# Shutdown_2019_v1_1_1.net
KiCad netlist of a schematic drawn in Altium Designer
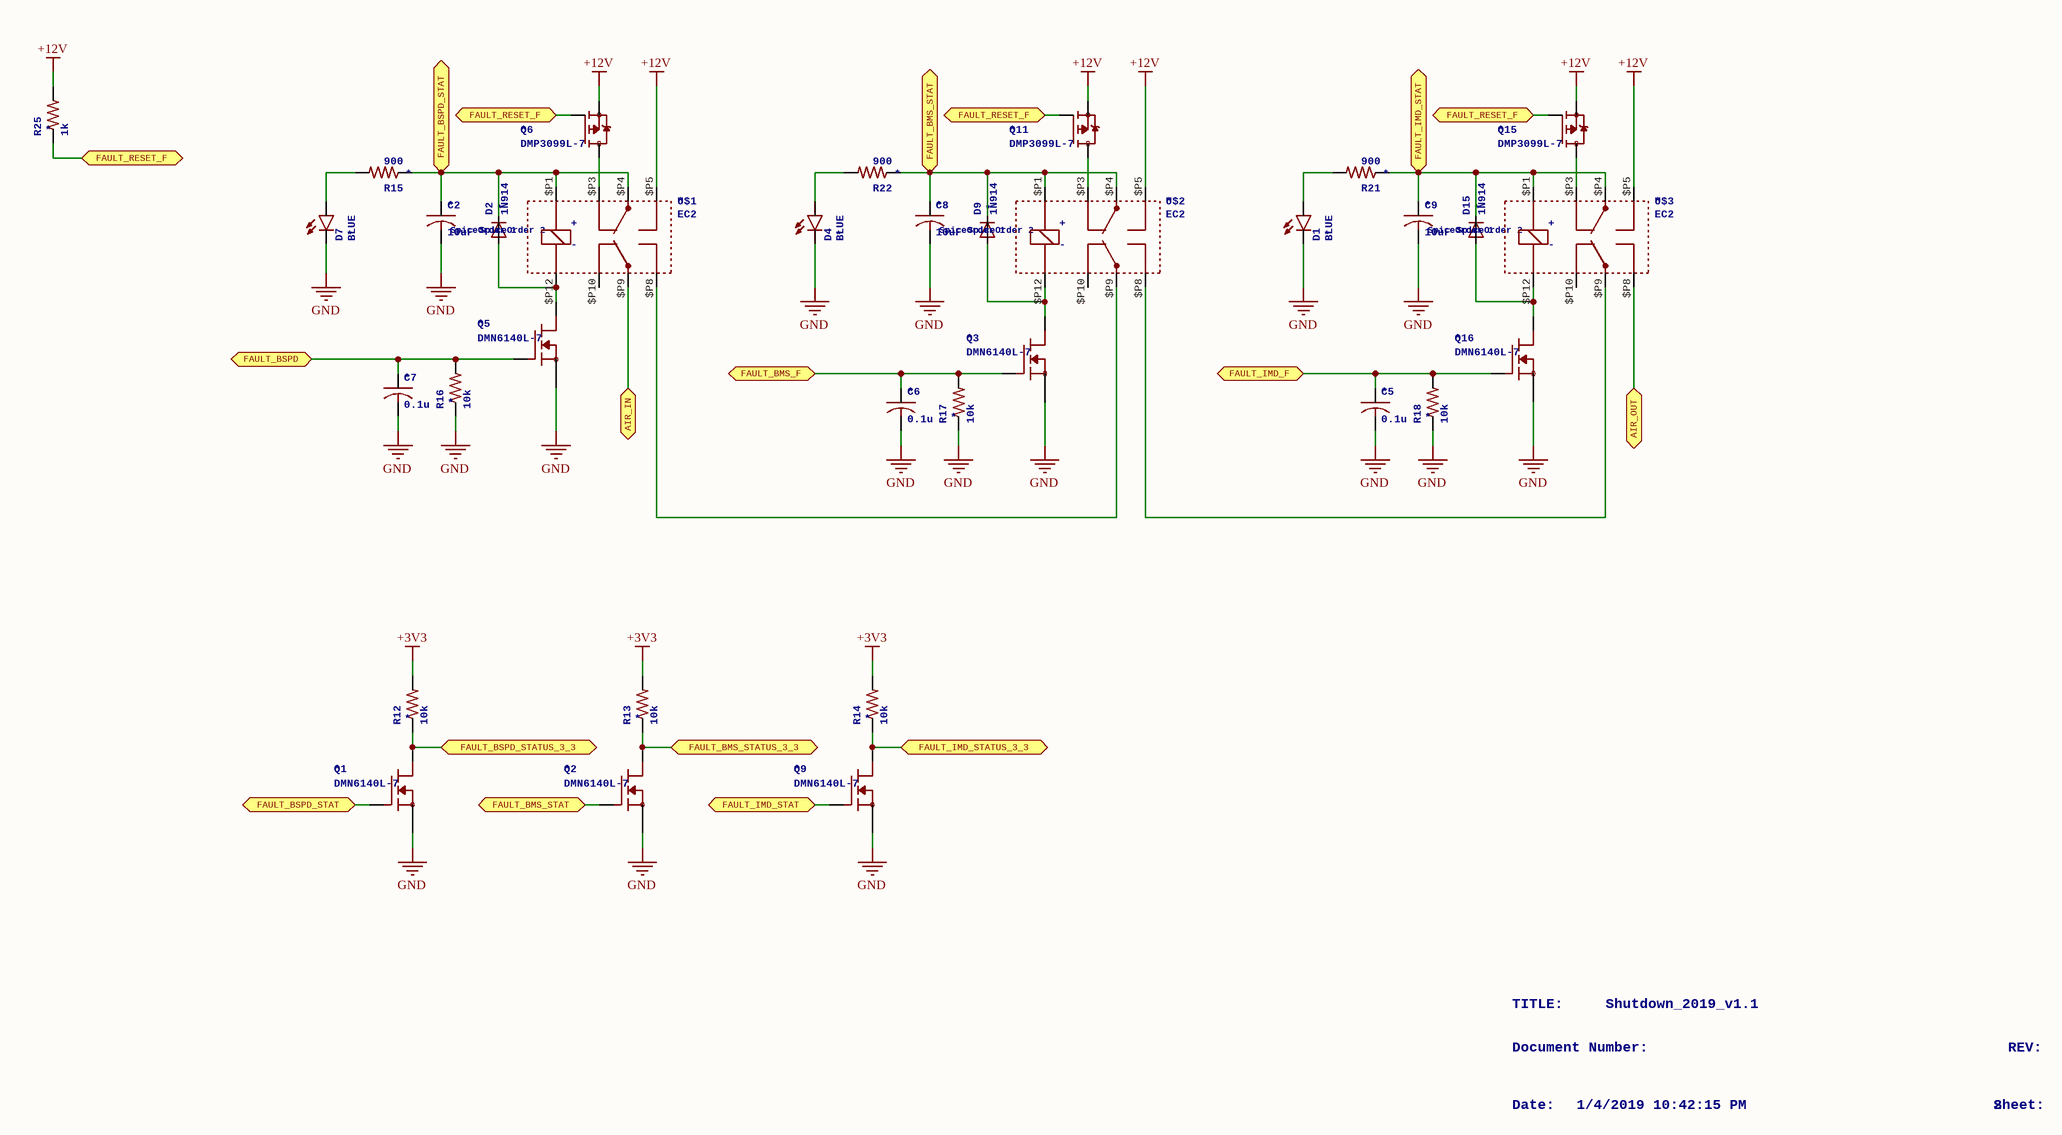
[diagram p0: Shutdown_2019_v1.1_1.SchDoc]

(export (version "E")
  (design (tool "Eeschema 10.0.6"))
  (components
    (comp (ref "C2")
      (value "10uF")
      (footprint "C0805")
      (description "CAPACITOR, American symbol")
      (fields (field (name "NAME") "*"))
      (libsource (lib "rcl") (part "C-USC0805"))
    )
    (comp (ref "C5")
      (value "0.1u")
      (footprint "C0603")
      (description "CAPACITOR, American symbol")
      (fields (field (name "NAME") "*"))
      (libsource (lib "resistor") (part "C-USC0603"))
    )
    (comp (ref "C6")
      (value "0.1u")
      (footprint "C0603")
      (description "CAPACITOR, American symbol")
      (fields (field (name "NAME") "*"))
      (libsource (lib "resistor") (part "C-USC0603"))
    )
    (comp (ref "C7")
      (value "0.1u")
      (footprint "C0603")
      (description "CAPACITOR, American symbol")
      (fields (field (name "NAME") "*"))
      (libsource (lib "resistor") (part "C-USC0603"))
    )
    (comp (ref "C8")
      (value "10uF")
      (footprint "C0805")
      (description "CAPACITOR, American symbol")
      (fields (field (name "NAME") "*"))
      (libsource (lib "rcl") (part "C-USC0805"))
    )
    (comp (ref "C9")
      (value "10uF")
      (footprint "C0805")
      (description "CAPACITOR, American symbol")
      (fields (field (name "NAME") "*"))
      (libsource (lib "rcl") (part "C-USC0805"))
    )
    (comp (ref "D1")
      (value "BLUE")
      (footprint "LED-0603")
      (fields (field (name "NAME") "*"))
      (libsource (lib "SparkFun-LED") (part "LED-BLUE0603"))
    )
    (comp (ref "D2")
      (value "1N914")
      (footprint "SOD323-F")
      (fields
        (field (name "NAME") "*")
        (field (name "SPICEORDER1") "SpiceOrder 1")
        (field (name "SPICEORDER2") "SpiceOrder 2")
      )
      (libsource (lib "Diodes") (part "1N914"))
    )
    (comp (ref "D4")
      (value "BLUE")
      (footprint "LED-0603")
      (fields (field (name "NAME") "*"))
      (libsource (lib "SparkFun-LED") (part "LED-BLUE0603"))
    )
    (comp (ref "D7")
      (value "BLUE")
      (footprint "LED-0603")
      (fields (field (name "NAME") "*"))
      (libsource (lib "SparkFun-LED") (part "LED-BLUE0603"))
    )
    (comp (ref "D9")
      (value "1N914")
      (footprint "SOD323-F")
      (fields
        (field (name "NAME") "*")
        (field (name "SPICEORDER1") "SpiceOrder 1")
        (field (name "SPICEORDER2") "SpiceOrder 2")
      )
      (libsource (lib "Diodes") (part "1N914"))
    )
    (comp (ref "D15")
      (value "1N914")
      (footprint "SOD323-F")
      (fields
        (field (name "NAME") "*")
        (field (name "SPICEORDER1") "SpiceOrder 1")
        (field (name "SPICEORDER2") "SpiceOrder 2")
      )
      (libsource (lib "Diodes") (part "1N914"))
    )
    (comp (ref "Q1")
      (value "DMN6140L-7")
      (footprint "SOT23")
      (description "DMN6140L-7 Vgs(th) = 3V, Rds(on) = 140mOhm, Vds(max) = 60V")
      (fields (field (name "NAME") "*"))
      (libsource (lib "TRANS") (part "DMN6140L-7"))
    )
    (comp (ref "Q2")
      (value "DMN6140L-7")
      (footprint "SOT23")
      (description "DMN6140L-7 Vgs(th) = 3V, Rds(on) = 140mOhm, Vds(max) = 60V")
      (fields (field (name "NAME") "*"))
      (libsource (lib "TRANS") (part "DMN6140L-7"))
    )
    (comp (ref "Q3")
      (value "DMN6140L-7")
      (footprint "SOT23")
      (description "DMN6140L-7 Vgs(th) = 3V, Rds(on) = 140mOhm, Vds(max) = 60V")
      (fields (field (name "NAME") "*"))
      (libsource (lib "TRANS") (part "DMN6140L-7"))
    )
    (comp (ref "Q5")
      (value "DMN6140L-7")
      (footprint "SOT23")
      (description "DMN6140L-7 Vgs(th) = 3V, Rds(on) = 140mOhm, Vds(max) = 60V")
      (fields (field (name "NAME") "*"))
      (libsource (lib "TRANS") (part "DMN6140L-7"))
    )
    (comp (ref "Q6")
      (value "DMP3099L-7")
      (footprint "SOT23")
      (description "DMP3099L-7  P-Channel Vgs(th) = 2.1V, Rds(on) = 64 mohm, Vds(max) = 30V")
      (fields (field (name "NAME") "*"))
      (libsource (lib "TRANS") (part "DMP3099L-7"))
    )
    (comp (ref "Q9")
      (value "DMN6140L-7")
      (footprint "SOT23")
      (description "DMN6140L-7 Vgs(th) = 3V, Rds(on) = 140mOhm, Vds(max) = 60V")
      (fields (field (name "NAME") "*"))
      (libsource (lib "TRANS") (part "DMN6140L-7"))
    )
    (comp (ref "Q11")
      (value "DMP3099L-7")
      (footprint "SOT23")
      (description "DMP3099L-7  P-Channel Vgs(th) = 2.1V, Rds(on) = 64 mohm, Vds(max) = 30V")
      (fields (field (name "NAME") "*"))
      (libsource (lib "TRANS") (part "DMP3099L-7"))
    )
    (comp (ref "Q15")
      (value "DMP3099L-7")
      (footprint "SOT23")
      (description "DMP3099L-7  P-Channel Vgs(th) = 2.1V, Rds(on) = 64 mohm, Vds(max) = 30V")
      (fields (field (name "NAME") "*"))
      (libsource (lib "TRANS") (part "DMP3099L-7"))
    )
    (comp (ref "Q16")
      (value "DMN6140L-7")
      (footprint "SOT23")
      (description "DMN6140L-7 Vgs(th) = 3V, Rds(on) = 140mOhm, Vds(max) = 60V")
      (fields (field (name "NAME") "*"))
      (libsource (lib "TRANS") (part "DMN6140L-7"))
    )
    (comp (ref "R12")
      (value "10k")
      (footprint "R0603")
      (description "RESISTOR, American symbol")
      (fields (field (name "NAME") "*"))
      (libsource (lib "resistor") (part "R-US_R0603"))
    )
    (comp (ref "R13")
      (value "10k")
      (footprint "R0603")
      (description "RESISTOR, American symbol")
      (fields (field (name "NAME") "*"))
      (libsource (lib "resistor") (part "R-US_R0603"))
    )
    (comp (ref "R14")
      (value "10k")
      (footprint "R0603")
      (description "RESISTOR, American symbol")
      (fields (field (name "NAME") "*"))
      (libsource (lib "resistor") (part "R-US_R0603"))
    )
    (comp (ref "R15")
      (value "900")
      (footprint "R0603")
      (description "RESISTOR, American symbol")
      (fields (field (name "NAME") "*"))
      (libsource (lib "resistor") (part "R-US_R0603"))
    )
    (comp (ref "R16")
      (value "10k")
      (footprint "R0603")
      (description "RESISTOR, American symbol")
      (fields (field (name "NAME") "*"))
      (libsource (lib "resistor") (part "R-US_R0603"))
    )
    (comp (ref "R17")
      (value "10k")
      (footprint "R0603")
      (description "RESISTOR, American symbol")
      (fields (field (name "NAME") "*"))
      (libsource (lib "resistor") (part "R-US_R0603"))
    )
    (comp (ref "R18")
      (value "10k")
      (footprint "R0603")
      (description "RESISTOR, American symbol")
      (fields (field (name "NAME") "*"))
      (libsource (lib "resistor") (part "R-US_R0603"))
    )
    (comp (ref "R21")
      (value "900")
      (footprint "R0603")
      (description "RESISTOR, American symbol")
      (fields (field (name "NAME") "*"))
      (libsource (lib "resistor") (part "R-US_R0603"))
    )
    (comp (ref "R22")
      (value "900")
      (footprint "R0603")
      (description "RESISTOR, American symbol")
      (fields (field (name "NAME") "*"))
      (libsource (lib "resistor") (part "R-US_R0603"))
    )
    (comp (ref "R25")
      (value "1k")
      (footprint "R0603")
      (description "RESISTOR, American symbol")
      (fields (field (name "NAME") "*"))
      (libsource (lib "resistor") (part "R-US_R0603"))
    )
    (comp (ref "U$1")
      (value "EC2")
      (footprint "DPDT_2.54")
      (description "KEMET EC2 DPDT General Purpose 2A Relay. 12V coil voltage.Datasheet Digikey")
      (fields (field (name "NAME") "*") (field (name "+") "+") (field (name "-") "-"))
      (libsource (lib "KEMET") (part "EC2"))
    )
    (comp (ref "U$2")
      (value "EC2")
      (footprint "DPDT_2.54")
      (description "KEMET EC2 DPDT General Purpose 2A Relay. 12V coil voltage.Datasheet Digikey")
      (fields (field (name "NAME") "*") (field (name "+") "+") (field (name "-") "-"))
      (libsource (lib "KEMET") (part "EC2"))
    )
    (comp (ref "U$3")
      (value "EC2")
      (footprint "DPDT_2.54")
      (description "KEMET EC2 DPDT General Purpose 2A Relay. 12V coil voltage.Datasheet Digikey")
      (fields (field (name "NAME") "*") (field (name "+") "+") (field (name "-") "-"))
      (libsource (lib "KEMET") (part "EC2"))
    )
  )
  (nets
    (net (code "1") (name "+3V3") (class "Default")
      (node (ref "R12") (pin "2") (pinfunction "2_2") (pintype "passive"))
      (node (ref "R13") (pin "2") (pinfunction "2_2") (pintype "passive"))
      (node (ref "R14") (pin "2") (pinfunction "2_2") (pintype "passive"))
    )
    (net (code "2") (name "+12V") (class "Default")
      (node (ref "Q11") (pin "2") (pinfunction "S_2") (pintype "passive"))
      (node (ref "Q15") (pin "2") (pinfunction "S_2") (pintype "passive"))
      (node (ref "Q6") (pin "2") (pinfunction "S_2") (pintype "passive"))
      (node (ref "R25") (pin "2") (pinfunction "2_2") (pintype "passive"))
      (node (ref "U$1") (pin "$P5") (pinfunction "$P5_$P5") (pintype "passive"))
      (node (ref "U$2") (pin "$P5") (pinfunction "$P5_$P5") (pintype "passive"))
      (node (ref "U$3") (pin "$P5") (pinfunction "$P5_$P5") (pintype "passive"))
    )
    (net (code "3") (name "/AIR_IN") (class "Default")
      (node (ref "U$1") (pin "$P9") (pinfunction "$P9_$P9") (pintype "passive"))
    )
    (net (code "4") (name "/AIR_OUT") (class "Default")
      (node (ref "U$3") (pin "$P8") (pinfunction "$P8_$P8") (pintype "passive"))
    )
    (net (code "5") (name "/FAULT_BMS_F") (class "Default")
      (node (ref "C6") (pin "1") (pinfunction "1_1") (pintype "passive"))
      (node (ref "Q3") (pin "1") (pinfunction "G_1") (pintype "passive"))
      (node (ref "R17") (pin "2") (pinfunction "2_2") (pintype "passive"))
    )
    (net (code "6") (name "/FAULT_BMS_STAT") (class "Default")
      (node (ref "C8") (pin "1") (pinfunction "1_1") (pintype "passive"))
      (node (ref "D9") (pin "C") (pinfunction "C_C") (pintype "passive"))
      (node (ref "Q2") (pin "1") (pinfunction "G_1") (pintype "passive"))
      (node (ref "R22") (pin "1") (pinfunction "1_1") (pintype "passive"))
      (node (ref "U$2") (pin "$P1") (pinfunction "$P1_$P1") (pintype "passive"))
      (node (ref "U$2") (pin "$P4") (pinfunction "$P4_$P4") (pintype "passive"))
    )
    (net (code "7") (name "/FAULT_BMS_STATUS_3_3") (class "Default")
      (node (ref "Q2") (pin "3") (pinfunction "D_3") (pintype "passive"))
      (node (ref "R13") (pin "1") (pinfunction "1_1") (pintype "passive"))
    )
    (net (code "8") (name "/FAULT_BSPD") (class "Default")
      (node (ref "C7") (pin "1") (pinfunction "1_1") (pintype "passive"))
      (node (ref "Q5") (pin "1") (pinfunction "G_1") (pintype "passive"))
      (node (ref "R16") (pin "2") (pinfunction "2_2") (pintype "passive"))
    )
    (net (code "9") (name "/FAULT_BSPD_STAT") (class "Default")
      (node (ref "C2") (pin "1") (pinfunction "1_1") (pintype "passive"))
      (node (ref "D2") (pin "C") (pinfunction "C_C") (pintype "passive"))
      (node (ref "Q1") (pin "1") (pinfunction "G_1") (pintype "passive"))
      (node (ref "R15") (pin "1") (pinfunction "1_1") (pintype "passive"))
      (node (ref "U$1") (pin "$P1") (pinfunction "$P1_$P1") (pintype "passive"))
      (node (ref "U$1") (pin "$P4") (pinfunction "$P4_$P4") (pintype "passive"))
    )
    (net (code "10") (name "/FAULT_BSPD_STATUS_3_3") (class "Default")
      (node (ref "Q1") (pin "3") (pinfunction "D_3") (pintype "passive"))
      (node (ref "R12") (pin "1") (pinfunction "1_1") (pintype "passive"))
    )
    (net (code "11") (name "/FAULT_IMD_F") (class "Default")
      (node (ref "C5") (pin "1") (pinfunction "1_1") (pintype "passive"))
      (node (ref "Q16") (pin "1") (pinfunction "G_1") (pintype "passive"))
      (node (ref "R18") (pin "2") (pinfunction "2_2") (pintype "passive"))
    )
    (net (code "12") (name "/FAULT_IMD_STAT") (class "Default")
      (node (ref "C9") (pin "1") (pinfunction "1_1") (pintype "passive"))
      (node (ref "D15") (pin "C") (pinfunction "C_C") (pintype "passive"))
      (node (ref "Q9") (pin "1") (pinfunction "G_1") (pintype "passive"))
      (node (ref "R21") (pin "1") (pinfunction "1_1") (pintype "passive"))
      (node (ref "U$3") (pin "$P1") (pinfunction "$P1_$P1") (pintype "passive"))
      (node (ref "U$3") (pin "$P4") (pinfunction "$P4_$P4") (pintype "passive"))
    )
    (net (code "13") (name "/FAULT_IMD_STATUS_3_3") (class "Default")
      (node (ref "Q9") (pin "3") (pinfunction "D_3") (pintype "passive"))
      (node (ref "R14") (pin "1") (pinfunction "1_1") (pintype "passive"))
    )
    (net (code "14") (name "/FAULT_RESET_F") (class "Default")
      (node (ref "Q11") (pin "1") (pinfunction "G_1") (pintype "passive"))
      (node (ref "Q15") (pin "1") (pinfunction "G_1") (pintype "passive"))
      (node (ref "Q6") (pin "1") (pinfunction "G_1") (pintype "passive"))
      (node (ref "R25") (pin "1") (pinfunction "1_1") (pintype "passive"))
    )
    (net (code "15") (name "GND") (class "Default")
      (node (ref "C2") (pin "2") (pinfunction "2_2") (pintype "passive"))
      (node (ref "C5") (pin "2") (pinfunction "2_2") (pintype "passive"))
      (node (ref "C6") (pin "2") (pinfunction "2_2") (pintype "passive"))
      (node (ref "C7") (pin "2") (pinfunction "2_2") (pintype "passive"))
      (node (ref "C8") (pin "2") (pinfunction "2_2") (pintype "passive"))
      (node (ref "C9") (pin "2") (pinfunction "2_2") (pintype "passive"))
      (node (ref "D1") (pin "C") (pinfunction "C_C") (pintype "passive"))
      (node (ref "D4") (pin "C") (pinfunction "C_C") (pintype "passive"))
      (node (ref "D7") (pin "C") (pinfunction "C_C") (pintype "passive"))
      (node (ref "Q1") (pin "2") (pinfunction "S_2") (pintype "passive"))
      (node (ref "Q16") (pin "2") (pinfunction "S_2") (pintype "passive"))
      (node (ref "Q2") (pin "2") (pinfunction "S_2") (pintype "passive"))
      (node (ref "Q3") (pin "2") (pinfunction "S_2") (pintype "passive"))
      (node (ref "Q5") (pin "2") (pinfunction "S_2") (pintype "passive"))
      (node (ref "Q9") (pin "2") (pinfunction "S_2") (pintype "passive"))
      (node (ref "R16") (pin "1") (pinfunction "1_1") (pintype "passive"))
      (node (ref "R17") (pin "1") (pinfunction "1_1") (pintype "passive"))
      (node (ref "R18") (pin "1") (pinfunction "1_1") (pintype "passive"))
    )
    (net (code "16") (name "Net-(D1-PadA)") (class "Default")
      (node (ref "D1") (pin "A") (pinfunction "A_A") (pintype "passive"))
      (node (ref "R21") (pin "2") (pinfunction "2_2") (pintype "passive"))
    )
    (net (code "17") (name "Net-(D4-PadA)") (class "Default")
      (node (ref "D4") (pin "A") (pinfunction "A_A") (pintype "passive"))
      (node (ref "R22") (pin "2") (pinfunction "2_2") (pintype "passive"))
    )
    (net (code "18") (name "Net-(D7-PadA)") (class "Default")
      (node (ref "D7") (pin "A") (pinfunction "A_A") (pintype "passive"))
      (node (ref "R15") (pin "2") (pinfunction "2_2") (pintype "passive"))
    )
    (net (code "19") (name "Net-(Q3-D)") (class "Default")
      (node (ref "D9") (pin "A") (pinfunction "A_A") (pintype "passive"))
      (node (ref "Q3") (pin "3") (pinfunction "D_3") (pintype "passive"))
      (node (ref "U$2") (pin "$P12") (pinfunction "$P12_$P12") (pintype "passive"))
    )
    (net (code "20") (name "Net-(Q5-D)") (class "Default")
      (node (ref "D2") (pin "A") (pinfunction "A_A") (pintype "passive"))
      (node (ref "Q5") (pin "3") (pinfunction "D_3") (pintype "passive"))
      (node (ref "U$1") (pin "$P12") (pinfunction "$P12_$P12") (pintype "passive"))
    )
    (net (code "21") (name "Net-(Q6-D)") (class "Default")
      (node (ref "Q6") (pin "3") (pinfunction "D_3") (pintype "passive"))
      (node (ref "U$1") (pin "$P3") (pinfunction "$P3_$P3") (pintype "passive"))
    )
    (net (code "22") (name "Net-(Q11-D)") (class "Default")
      (node (ref "Q11") (pin "3") (pinfunction "D_3") (pintype "passive"))
      (node (ref "U$2") (pin "$P3") (pinfunction "$P3_$P3") (pintype "passive"))
    )
    (net (code "23") (name "Net-(Q15-D)") (class "Default")
      (node (ref "Q15") (pin "3") (pinfunction "D_3") (pintype "passive"))
      (node (ref "U$3") (pin "$P3") (pinfunction "$P3_$P3") (pintype "passive"))
    )
    (net (code "24") (name "Net-(Q16-D)") (class "Default")
      (node (ref "D15") (pin "A") (pinfunction "A_A") (pintype "passive"))
      (node (ref "Q16") (pin "3") (pinfunction "D_3") (pintype "passive"))
      (node (ref "U$3") (pin "$P12") (pinfunction "$P12_$P12") (pintype "passive"))
    )
    (net (code "25") (name "Net-(U$1-Pad$P8)") (class "Default")
      (node (ref "U$1") (pin "$P8") (pinfunction "$P8_$P8") (pintype "passive"))
      (node (ref "U$2") (pin "$P9") (pinfunction "$P9_$P9") (pintype "passive"))
    )
    (net (code "26") (name "Net-(U$2-Pad$P8)") (class "Default")
      (node (ref "U$2") (pin "$P8") (pinfunction "$P8_$P8") (pintype "passive"))
      (node (ref "U$3") (pin "$P9") (pinfunction "$P9_$P9") (pintype "passive"))
    )
    (net (code "27") (name "unconnected-(U$1-Pad$P10)") (class "Default")
      (node (ref "U$1") (pin "$P10") (pinfunction "$P10_$P10") (pintype "passive"))
    )
    (net (code "28") (name "unconnected-(U$2-Pad$P10)") (class "Default")
      (node (ref "U$2") (pin "$P10") (pinfunction "$P10_$P10") (pintype "passive"))
    )
    (net (code "29") (name "unconnected-(U$3-Pad$P10)") (class "Default")
      (node (ref "U$3") (pin "$P10") (pinfunction "$P10_$P10") (pintype "passive"))
    )
  )
)
